# gydrodrive_i2c.net
KiCad netlist of a schematic drawn in Altium Designer
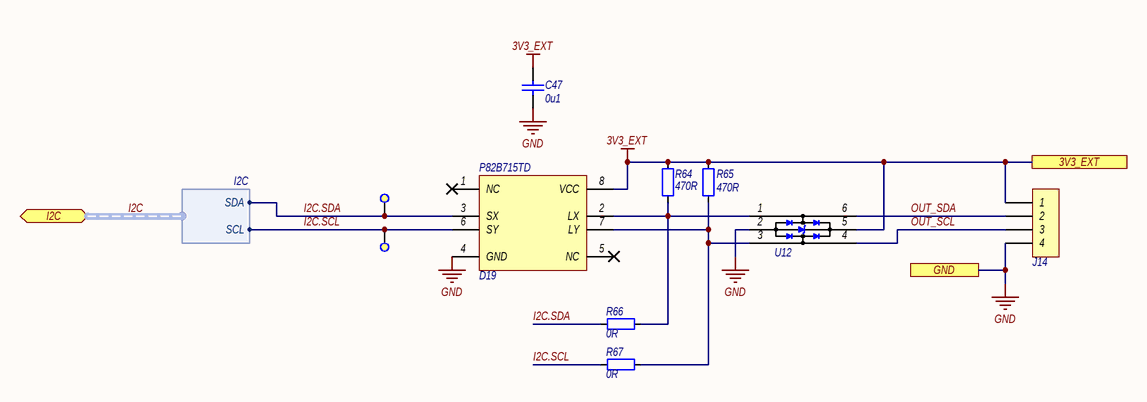
[diagram p0: gydrodrive_i2c.SchDoc]

(export (version "E")
  (design (tool "Eeschema 10.0.6"))
  (components
    (comp (ref "C47")
      (value "CAP_0805")
      (footprint "CAPC2012-0805M")
      (description "Конденсатор керамический, корпус 0805")
      (fields
        (field (name "CAPACITANCE") "0u1")
        (field (name "PART NUMBER") "CAPC_0805")
        (field (name "VOLTAGE") "50V")
      )
      (libsource (lib "StdLib") (part "CAP"))
    )
    (comp (ref "D19")
      (value "P82B715TD")
      (footprint "SO8_M")
      (description "Расширитель порта I2C")
      (libsource (lib "StdLib") (part "P82B715TD"))
    )
    (comp (ref "J14")
      (value "DG142V-5.08-04P")
      (footprint "DG142V-5.08-04P")
      (description "Клеммник 4-контактный, шаг 5.08 мм")
      (libsource (lib "StdLib") (part "PIN1x4"))
    )
    (comp (ref "R64")
      (value "RES_0805")
      (footprint "RESC2012-0805M")
      (description "Рез-р, корпус 0805")
      (fields
        (field (name "RESISTANCE") "470R")
        (field (name "PART NUMBER") "RESC_0805")
        (field (name "TOLERANCE") "5%")
      )
      (libsource (lib "StdLib") (part "RES"))
    )
    (comp (ref "R65")
      (value "RES_0805")
      (footprint "RESC2012-0805M")
      (description "Рез-р, корпус 0805")
      (fields
        (field (name "RESISTANCE") "470R")
        (field (name "PART NUMBER") "RESC_0805")
        (field (name "TOLERANCE") "5%")
      )
      (libsource (lib "StdLib") (part "RES"))
    )
    (comp (ref "R66")
      (value "RES_0805")
      (footprint "RESC2012-0805M")
      (description "Рез-р, корпус 0805")
      (fields
        (field (name "RESISTANCE") "0R")
        (field (name "PART NUMBER") "RESC_0805")
        (field (name "TOLERANCE") "5%")
      )
      (libsource (lib "") (part "RES_1"))
    )
    (comp (ref "R67")
      (value "RES_0805")
      (footprint "RESC2012-0805M")
      (description "Рез-р, корпус 0805")
      (fields
        (field (name "RESISTANCE") "0R")
        (field (name "PART NUMBER") "RESC_0805")
        (field (name "TOLERANCE") "5%")
      )
      (libsource (lib "") (part "RES_1"))
    )
    (comp (ref "TP16")
      (value "Test point 1")
      (footprint "TP_1")
      (description "Тестовый контакт круглый 1 мм")
      (libsource (lib "StdLib") (part "Test point"))
    )
    (comp (ref "TP17")
      (value "Test point 1")
      (footprint "TP_1")
      (description "Тестовый контакт круглый 1 мм")
      (libsource (lib "StdLib") (part "Test point"))
    )
    (comp (ref "U12")
      (value "USBLC6-2SC6")
      (footprint "SOT23-6AM")
      (description "Диодная сборка для защиты дифференциальной линии")
      (fields (field (name "VOLTAGE") "5.25V"))
      (libsource (lib "StdLib") (part "USBLC6-2SC6"))
    )
  )
  (nets
    (net (code "2") (name "/I2C.SCL") (class "Default")
      (node (ref "D19") (pin "6") (pinfunction "SY_6") (pintype "passive"))
      (node (ref "R67") (pin "1") (pinfunction "1_1") (pintype "passive"))
      (node (ref "TP17") (pin "1") (pinfunction "1_1") (pintype "passive"))
    )
    (net (code "3") (name "/I2C.SDA") (class "Default")
      (node (ref "D19") (pin "3") (pinfunction "SX_3") (pintype "passive"))
      (node (ref "R66") (pin "1") (pinfunction "1_1") (pintype "passive"))
      (node (ref "TP16") (pin "1") (pinfunction "1_1") (pintype "passive"))
    )
    (net (code "5") (name "/OUT_SCL") (class "Default")
      (node (ref "J14") (pin "3") (pinfunction "3_3") (pintype "passive"))
      (node (ref "U12") (pin "4") (pinfunction "IO2_4") (pintype "passive"))
    )
    (net (code "6") (name "/OUT_SDA") (class "Default")
      (node (ref "J14") (pin "2") (pinfunction "2_2") (pintype "passive"))
      (node (ref "U12") (pin "6") (pinfunction "IO1_6") (pintype "passive"))
    )
    (net (code "7") (name "3V3_EXT") (class "Default")
      (node (ref "C47") (pin "1") (pinfunction "1_1") (pintype "passive"))
      (node (ref "D19") (pin "8") (pinfunction "VCC_8") (pintype "passive"))
      (node (ref "J14") (pin "1") (pinfunction "1_1") (pintype "passive"))
      (node (ref "R64") (pin "2") (pinfunction "2_2") (pintype "passive"))
      (node (ref "R65") (pin "2") (pinfunction "2_2") (pintype "passive"))
      (node (ref "U12") (pin "5") (pinfunction "Vbus_5") (pintype "passive"))
    )
    (net (code "8") (name "GND") (class "Default")
      (node (ref "C47") (pin "2") (pinfunction "2_2") (pintype "passive"))
      (node (ref "D19") (pin "4") (pinfunction "GND_4") (pintype "passive"))
      (node (ref "J14") (pin "4") (pinfunction "4_4") (pintype "passive"))
      (node (ref "U12") (pin "2") (pinfunction "GND_2") (pintype "passive"))
    )
    (net (code "9") (name "Net-(D19-LX)") (class "Default")
      (node (ref "D19") (pin "2") (pinfunction "LX_2") (pintype "passive"))
      (node (ref "R64") (pin "1") (pinfunction "1_1") (pintype "passive"))
      (node (ref "R66") (pin "2") (pinfunction "2_2") (pintype "passive"))
      (node (ref "U12") (pin "1") (pinfunction "IO1_1") (pintype "passive"))
    )
    (net (code "10") (name "Net-(D19-LY)") (class "Default")
      (node (ref "D19") (pin "7") (pinfunction "LY_7") (pintype "passive"))
      (node (ref "R65") (pin "1") (pinfunction "1_1") (pintype "passive"))
      (node (ref "R67") (pin "2") (pinfunction "2_2") (pintype "passive"))
      (node (ref "U12") (pin "3") (pinfunction "IO2_3") (pintype "passive"))
    )
    (net (code "11") (name "unconnected-(D19-NC-Pad1)") (class "Default")
      (node (ref "D19") (pin "1") (pinfunction "NC_1") (pintype "passive+no_connect"))
    )
    (net (code "12") (name "unconnected-(D19-NC-Pad5)") (class "Default")
      (node (ref "D19") (pin "5") (pinfunction "NC_5") (pintype "passive+no_connect"))
    )
  )
)
